# Aux_Board_V2.net
KiCad netlist of a schematic drawn in EAGLE
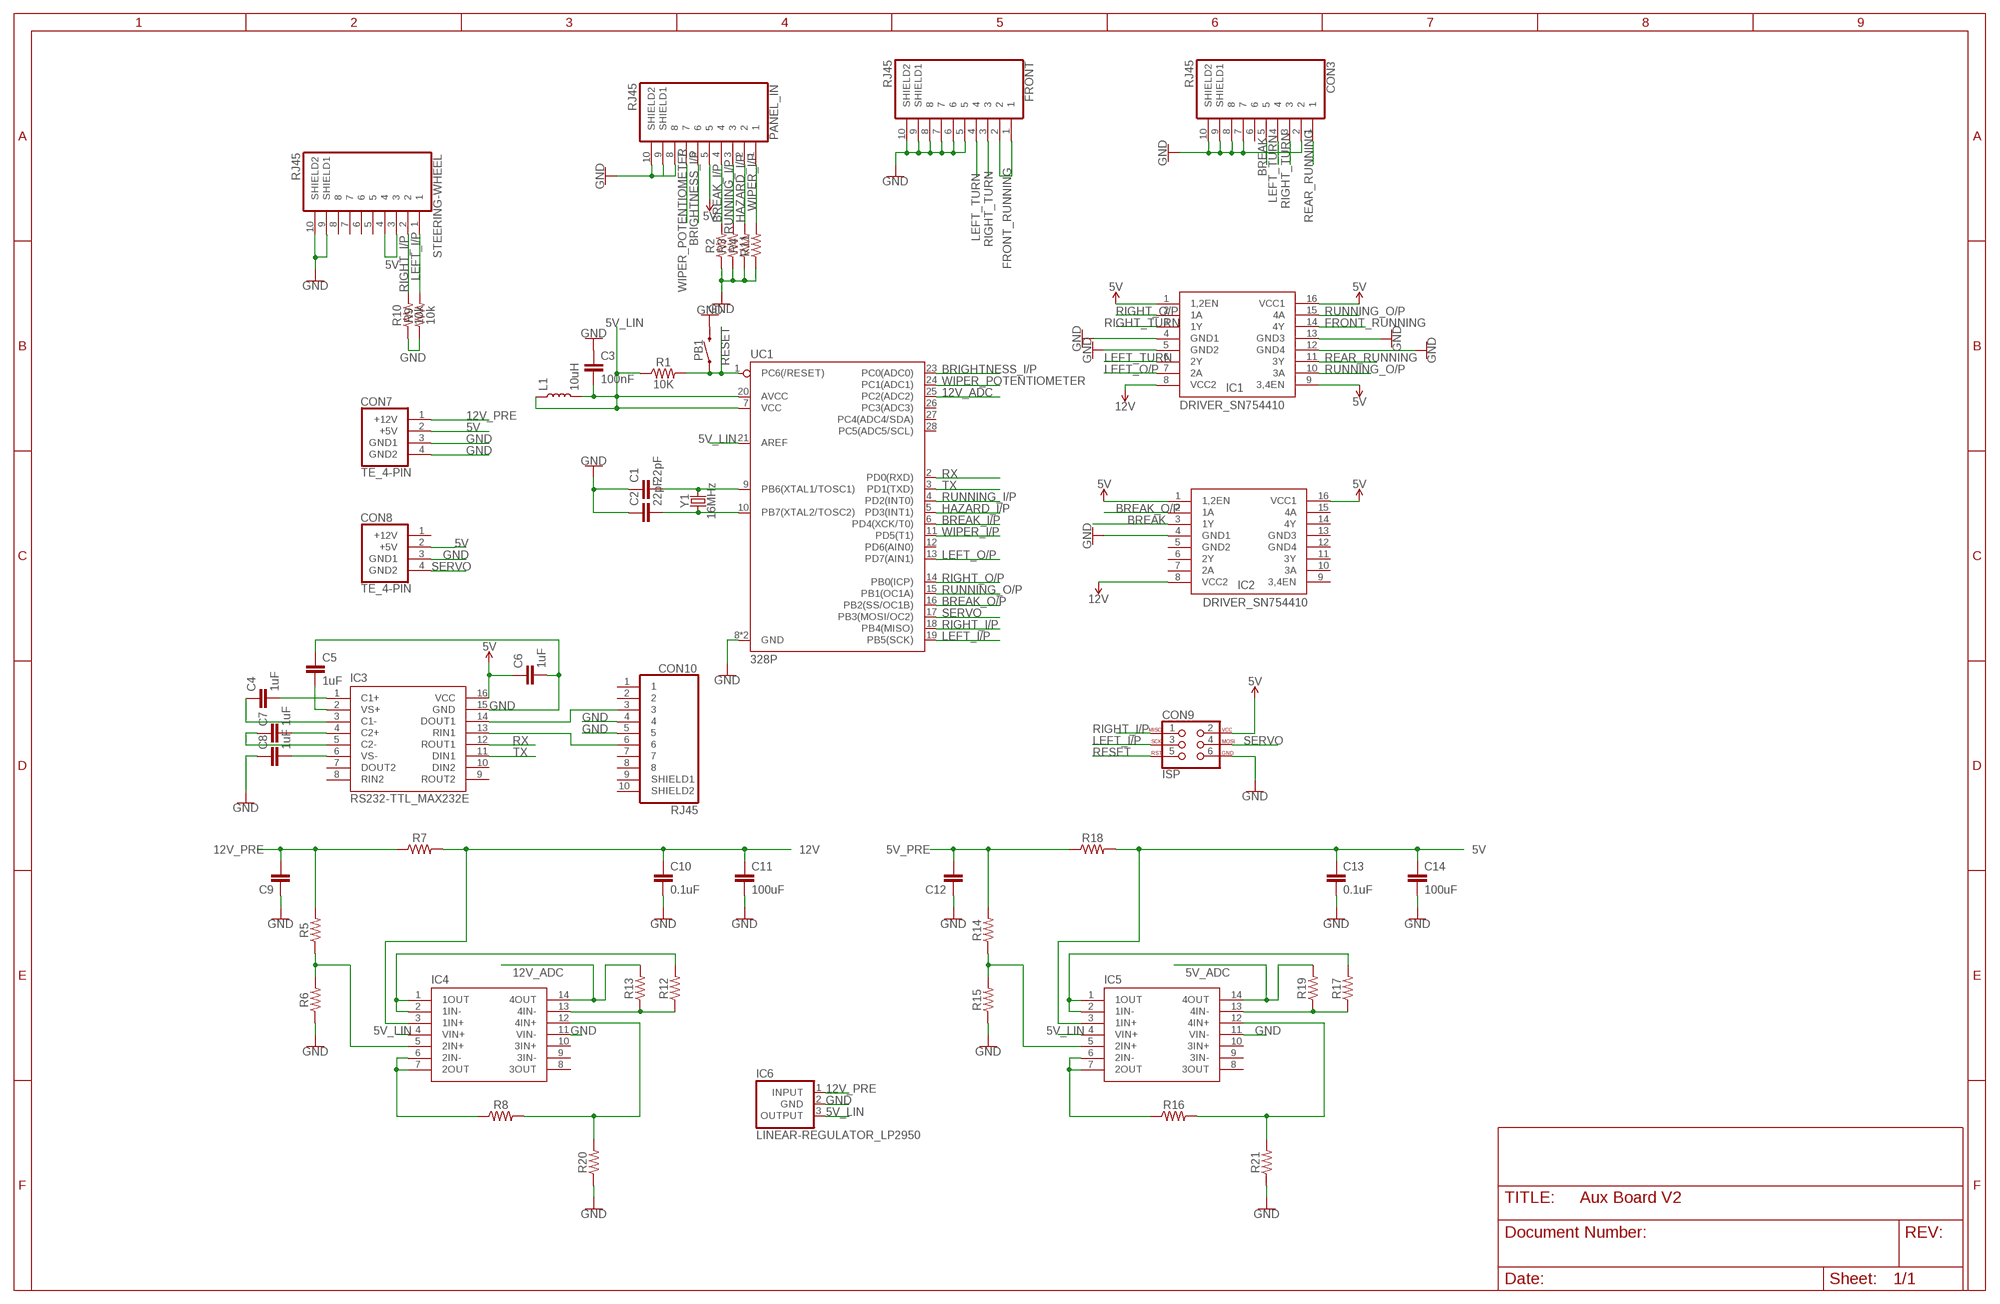
[diagram p0: schematic, sheet 1]

(export (version "E")
  (design (tool "Eeschema 10.0.6"))
  (components
    (comp (ref "C1")
      (value "22pF")
      (footprint "eagle-import:0805")
      (libsource (lib "eagle-import") (part "CAPACITOR_0805"))
    )
    (comp (ref "C2")
      (value "22pF")
      (footprint "eagle-import:0805")
      (libsource (lib "eagle-import") (part "CAPACITOR_0805"))
    )
    (comp (ref "C3")
      (value "100nF")
      (footprint "eagle-import:0805")
      (libsource (lib "eagle-import") (part "CAPACITOR_0805"))
    )
    (comp (ref "C4")
      (value "1uF")
      (footprint "eagle-import:0805")
      (libsource (lib "eagle-import") (part "CAPACITOR_0805"))
    )
    (comp (ref "C5")
      (value "1uF")
      (footprint "eagle-import:0805")
      (libsource (lib "eagle-import") (part "CAPACITOR_0805"))
    )
    (comp (ref "C6")
      (value "1uF")
      (footprint "eagle-import:0805")
      (libsource (lib "eagle-import") (part "CAPACITOR_0805"))
    )
    (comp (ref "C7")
      (value "1uF")
      (footprint "eagle-import:0805")
      (libsource (lib "eagle-import") (part "CAPACITOR_0805"))
    )
    (comp (ref "C8")
      (value "1uF")
      (footprint "eagle-import:0805")
      (libsource (lib "eagle-import") (part "CAPACITOR_0805"))
    )
    (comp (ref "C9")
      (value "CAPACITOR_0805")
      (footprint "eagle-import:0805")
      (libsource (lib "eagle-import") (part "CAPACITOR_0805"))
    )
    (comp (ref "C10")
      (value "0.1uF")
      (footprint "eagle-import:0805")
      (libsource (lib "eagle-import") (part "CAPACITOR_0805"))
    )
    (comp (ref "C11")
      (value "100uF")
      (footprint "eagle-import:0805")
      (libsource (lib "eagle-import") (part "CAPACITOR_0805"))
    )
    (comp (ref "C12")
      (value "CAPACITOR_0805")
      (footprint "eagle-import:0805")
      (libsource (lib "eagle-import") (part "CAPACITOR_0805"))
    )
    (comp (ref "C13")
      (value "0.1uF")
      (footprint "eagle-import:0805")
      (libsource (lib "eagle-import") (part "CAPACITOR_0805"))
    )
    (comp (ref "C14")
      (value "100uF")
      (footprint "eagle-import:0805")
      (libsource (lib "eagle-import") (part "CAPACITOR_0805"))
    )
    (comp (ref "CON3")
      (value "RJ45")
      (footprint "eagle-import:RJ45")
      (libsource (lib "eagle-import") (part "RJ45"))
    )
    (comp (ref "CON7")
      (value "TE_4-PIN")
      (footprint "eagle-import:TE_4-PIN")
      (libsource (lib "eagle-import") (part "TE_4-PIN"))
    )
    (comp (ref "CON8")
      (value "TE_4-PIN")
      (footprint "eagle-import:TE_4-PIN")
      (libsource (lib "eagle-import") (part "TE_4-PIN"))
    )
    (comp (ref "CON9")
      (value "ISP")
      (footprint "eagle-import:ISP_CONNECTOR")
      (libsource (lib "eagle-import") (part "ISP"))
    )
    (comp (ref "CON10")
      (value "RJ45")
      (footprint "eagle-import:RJ45")
      (libsource (lib "eagle-import") (part "RJ45"))
    )
    (comp (ref "FRONT")
      (value "RJ45")
      (footprint "eagle-import:RJ45")
      (libsource (lib "eagle-import") (part "RJ45"))
    )
    (comp (ref "IC1")
      (value "DRIVER_SN754410")
      (footprint "eagle-import:DIP16")
      (libsource (lib "eagle-import") (part "DRIVER_SN754410"))
    )
    (comp (ref "IC2")
      (value "DRIVER_SN754410")
      (footprint "eagle-import:DIP16")
      (libsource (lib "eagle-import") (part "DRIVER_SN754410"))
    )
    (comp (ref "IC3")
      (value "RS232-TTL_MAX232E")
      (footprint "eagle-import:DIP16")
      (libsource (lib "eagle-import") (part "RS232-TTL_MAX232E"))
    )
    (comp (ref "IC4")
      (value "OP-AMP_QUAD")
      (footprint "eagle-import:DIP14")
      (libsource (lib "eagle-import") (part "OP-AMP_QUAD"))
    )
    (comp (ref "IC5")
      (value "OP-AMP_QUAD")
      (footprint "eagle-import:DIP14")
      (libsource (lib "eagle-import") (part "OP-AMP_QUAD"))
    )
    (comp (ref "IC6")
      (value "LINEAR-REGULATOR_LP2950")
      (footprint "eagle-import:TO92")
      (libsource (lib "eagle-import") (part "LINEAR-REGULATOR_LP2950"))
    )
    (comp (ref "L1")
      (value "10uH")
      (footprint "eagle-import:0805")
      (libsource (lib "eagle-import") (part "INDUCTOR_0805"))
    )
    (comp (ref "PANEL_IN")
      (value "RJ45")
      (footprint "eagle-import:RJ45")
      (libsource (lib "eagle-import") (part "RJ45"))
    )
    (comp (ref "PB1")
      (value "PUSHBUTTON")
      (footprint "eagle-import:PUSHBUTTON")
      (libsource (lib "eagle-import") (part "PUSHBUTTON"))
    )
    (comp (ref "R1")
      (value "10K")
      (footprint "eagle-import:0805")
      (libsource (lib "eagle-import") (part "RESISTOR_0805"))
    )
    (comp (ref "R2")
      (value "RESISTOR_0805")
      (footprint "eagle-import:0805")
      (libsource (lib "eagle-import") (part "RESISTOR_0805"))
    )
    (comp (ref "R3")
      (value "RESISTOR_0805")
      (footprint "eagle-import:0805")
      (libsource (lib "eagle-import") (part "RESISTOR_0805"))
    )
    (comp (ref "R4")
      (value "RESISTOR_0805")
      (footprint "eagle-import:0805")
      (libsource (lib "eagle-import") (part "RESISTOR_0805"))
    )
    (comp (ref "R5")
      (value "RESISTOR_0805")
      (footprint "eagle-import:0805")
      (libsource (lib "eagle-import") (part "RESISTOR_0805"))
    )
    (comp (ref "R6")
      (value "RESISTOR_0805")
      (footprint "eagle-import:0805")
      (libsource (lib "eagle-import") (part "RESISTOR_0805"))
    )
    (comp (ref "R7")
      (value "RESISTOR_1210")
      (footprint "eagle-import:1210")
      (libsource (lib "eagle-import") (part "RESISTOR_1210"))
    )
    (comp (ref "R8")
      (value "RESISTOR_0805")
      (footprint "eagle-import:0805")
      (libsource (lib "eagle-import") (part "RESISTOR_0805"))
    )
    (comp (ref "R9")
      (value "10k")
      (footprint "eagle-import:0805")
      (libsource (lib "eagle-import") (part "RESISTOR_0805"))
    )
    (comp (ref "R10")
      (value "10k")
      (footprint "eagle-import:0805")
      (libsource (lib "eagle-import") (part "RESISTOR_0805"))
    )
    (comp (ref "R11")
      (value "RESISTOR_0805")
      (footprint "eagle-import:0805")
      (libsource (lib "eagle-import") (part "RESISTOR_0805"))
    )
    (comp (ref "R12")
      (value "RESISTOR_0805")
      (footprint "eagle-import:0805")
      (libsource (lib "eagle-import") (part "RESISTOR_0805"))
    )
    (comp (ref "R13")
      (value "RESISTOR_0805")
      (footprint "eagle-import:0805")
      (libsource (lib "eagle-import") (part "RESISTOR_0805"))
    )
    (comp (ref "R14")
      (value "RESISTOR_0805")
      (footprint "eagle-import:0805")
      (libsource (lib "eagle-import") (part "RESISTOR_0805"))
    )
    (comp (ref "R15")
      (value "RESISTOR_0805")
      (footprint "eagle-import:0805")
      (libsource (lib "eagle-import") (part "RESISTOR_0805"))
    )
    (comp (ref "R16")
      (value "RESISTOR_0805")
      (footprint "eagle-import:0805")
      (libsource (lib "eagle-import") (part "RESISTOR_0805"))
    )
    (comp (ref "R17")
      (value "RESISTOR_0805")
      (footprint "eagle-import:0805")
      (libsource (lib "eagle-import") (part "RESISTOR_0805"))
    )
    (comp (ref "R18")
      (value "RESISTOR_1210")
      (footprint "eagle-import:1210")
      (libsource (lib "eagle-import") (part "RESISTOR_1210"))
    )
    (comp (ref "R19")
      (value "RESISTOR_0805")
      (footprint "eagle-import:0805")
      (libsource (lib "eagle-import") (part "RESISTOR_0805"))
    )
    (comp (ref "R20")
      (value "RESISTOR_0805")
      (footprint "eagle-import:0805")
      (libsource (lib "eagle-import") (part "RESISTOR_0805"))
    )
    (comp (ref "R21")
      (value "RESISTOR_0805")
      (footprint "eagle-import:0805")
      (libsource (lib "eagle-import") (part "RESISTOR_0805"))
    )
    (comp (ref "STEERING-WHEEL")
      (value "RJ45")
      (footprint "eagle-import:RJ45")
      (libsource (lib "eagle-import") (part "RJ45"))
    )
    (comp (ref "UC1")
      (value "328P")
      (footprint "eagle-import:DIP28")
      (libsource (lib "eagle-import") (part "ATMEGA328P_DIP28"))
    )
    (comp (ref "Y1")
      (value "16MHz")
      (footprint "eagle-import:HC49US")
      (libsource (lib "eagle-import") (part "CRYSTAL-16MHZPTH-HC49US"))
    )
  )
  (nets
    (net (code "1") (name "/5V_ADC") (class "Default")
      (node (ref "IC5") (pin "14") (pinfunction "4OUT_14") (pintype "bidirectional"))
      (node (ref "R19") (pin "2") (pinfunction "2_2") (pintype "passive"))
    )
    (net (code "2") (name "/5V_LIN") (class "Default")
      (node (ref "C3") (pin "2") (pinfunction "2_2") (pintype "passive"))
      (node (ref "IC4") (pin "4") (pinfunction "VIN+_4") (pintype "bidirectional"))
      (node (ref "IC5") (pin "4") (pinfunction "VIN+_4") (pintype "bidirectional"))
      (node (ref "IC6") (pin "3") (pinfunction "OUTPUT_3") (pintype "bidirectional"))
      (node (ref "L1") (pin "1") (pinfunction "1_1") (pintype "passive"))
      (node (ref "L1") (pin "2") (pinfunction "2_2") (pintype "passive"))
      (node (ref "R1") (pin "1") (pinfunction "1_1") (pintype "passive"))
      (node (ref "UC1") (pin "20") (pinfunction "AVCC_20") (pintype "bidirectional"))
      (node (ref "UC1") (pin "21") (pinfunction "AREF_21") (pintype "bidirectional"))
      (node (ref "UC1") (pin "7") (pinfunction "VCC_7") (pintype "bidirectional"))
    )
    (net (code "3") (name "/5V_PRE") (class "Default")
      (node (ref "C12") (pin "2") (pinfunction "2_2") (pintype "passive"))
      (node (ref "R14") (pin "2") (pinfunction "2_2") (pintype "passive"))
      (node (ref "R18") (pin "1") (pinfunction "1_1") (pintype "passive"))
    )
    (net (code "4") (name "/12V_ADC") (class "Default")
      (node (ref "IC4") (pin "14") (pinfunction "4OUT_14") (pintype "bidirectional"))
      (node (ref "R13") (pin "2") (pinfunction "2_2") (pintype "passive"))
      (node (ref "UC1") (pin "25") (pinfunction "PC2(ADC2)_25") (pintype "bidirectional"))
    )
    (net (code "5") (name "/12V_PRE") (class "Default")
      (node (ref "C9") (pin "2") (pinfunction "2_2") (pintype "passive"))
      (node (ref "CON7") (pin "1") (pinfunction "+12V_1") (pintype "passive"))
      (node (ref "IC6") (pin "1") (pinfunction "INPUT_1") (pintype "bidirectional"))
      (node (ref "R5") (pin "2") (pinfunction "2_2") (pintype "passive"))
      (node (ref "R7") (pin "1") (pinfunction "1_1") (pintype "passive"))
    )
    (net (code "6") (name "/BREAK") (class "Default")
      (node (ref "CON3") (pin "5") (pinfunction "5_5") (pintype "passive"))
      (node (ref "IC2") (pin "3") (pinfunction "1Y_3") (pintype "bidirectional"))
    )
    (net (code "7") (name "/BREAK_I{slash}P") (class "Default")
      (node (ref "PANEL_IN") (pin "4") (pinfunction "4_4") (pintype "passive"))
      (node (ref "R2") (pin "2") (pinfunction "2_2") (pintype "passive"))
      (node (ref "UC1") (pin "6") (pinfunction "PD4(XCK/T0)_6") (pintype "bidirectional"))
    )
    (net (code "8") (name "/BREAK_O{slash}P") (class "Default")
      (node (ref "IC2") (pin "2") (pinfunction "1A_2") (pintype "bidirectional"))
      (node (ref "UC1") (pin "16") (pinfunction "PB2(SS/OC1B)_16") (pintype "bidirectional"))
    )
    (net (code "9") (name "/BRIGHTNESS_I{slash}P") (class "Default")
      (node (ref "PANEL_IN") (pin "6") (pinfunction "6_6") (pintype "passive"))
      (node (ref "UC1") (pin "23") (pinfunction "PC0(ADC0)_23") (pintype "bidirectional"))
    )
    (net (code "10") (name "/FRONT_RUNNING") (class "Default")
      (node (ref "FRONT") (pin "1") (pinfunction "1_1") (pintype "passive"))
      (node (ref "FRONT") (pin "2") (pinfunction "2_2") (pintype "passive"))
      (node (ref "IC1") (pin "14") (pinfunction "4Y_14") (pintype "bidirectional"))
    )
    (net (code "11") (name "/HAZARD_I{slash}P") (class "Default")
      (node (ref "PANEL_IN") (pin "2") (pinfunction "2_2") (pintype "passive"))
      (node (ref "R4") (pin "2") (pinfunction "2_2") (pintype "passive"))
      (node (ref "UC1") (pin "5") (pinfunction "PD3(INT1)_5") (pintype "bidirectional"))
    )
    (net (code "12") (name "/LEFT_I{slash}P") (class "Default")
      (node (ref "CON9") (pin "3") (pinfunction "3_3") (pintype "passive"))
      (node (ref "R9") (pin "2") (pinfunction "2_2") (pintype "passive"))
      (node (ref "STEERING-WHEEL") (pin "1") (pinfunction "1_1") (pintype "passive"))
      (node (ref "UC1") (pin "19") (pinfunction "PB5(SCK)_19") (pintype "bidirectional"))
    )
    (net (code "13") (name "/LEFT_O{slash}P") (class "Default")
      (node (ref "IC1") (pin "7") (pinfunction "2A_7") (pintype "bidirectional"))
      (node (ref "UC1") (pin "13") (pinfunction "PD7(AIN1)_13") (pintype "bidirectional"))
    )
    (net (code "14") (name "/LEFT_TURN") (class "Default")
      (node (ref "CON3") (pin "4") (pinfunction "4_4") (pintype "passive"))
      (node (ref "FRONT") (pin "4") (pinfunction "4_4") (pintype "passive"))
      (node (ref "IC1") (pin "6") (pinfunction "2Y_6") (pintype "bidirectional"))
    )
    (net (code "15") (name "/REAR_RUNNING") (class "Default")
      (node (ref "CON3") (pin "1") (pinfunction "1_1") (pintype "passive"))
      (node (ref "IC1") (pin "11") (pinfunction "3Y_11") (pintype "bidirectional"))
    )
    (net (code "16") (name "/RESET") (class "Default")
      (node (ref "CON9") (pin "5") (pinfunction "5_5") (pintype "passive"))
      (node (ref "PB1") (pin "1") (pinfunction "1_1") (pintype "passive"))
      (node (ref "PB1") (pin "2") (pinfunction "1_2") (pintype "passive"))
      (node (ref "R1") (pin "2") (pinfunction "2_2") (pintype "passive"))
      (node (ref "UC1") (pin "1") (pinfunction "PC6(/RESET)_1") (pintype "bidirectional"))
    )
    (net (code "17") (name "/RIGHT_I{slash}P") (class "Default")
      (node (ref "CON9") (pin "1") (pinfunction "1_1") (pintype "passive"))
      (node (ref "R10") (pin "2") (pinfunction "2_2") (pintype "passive"))
      (node (ref "STEERING-WHEEL") (pin "2") (pinfunction "2_2") (pintype "passive"))
      (node (ref "UC1") (pin "18") (pinfunction "PB4(MISO)_18") (pintype "bidirectional"))
    )
    (net (code "18") (name "/RIGHT_O{slash}P") (class "Default")
      (node (ref "IC1") (pin "2") (pinfunction "1A_2") (pintype "bidirectional"))
      (node (ref "UC1") (pin "14") (pinfunction "PB0(ICP)_14") (pintype "bidirectional"))
    )
    (net (code "19") (name "/RIGHT_TURN") (class "Default")
      (node (ref "CON3") (pin "3") (pinfunction "3_3") (pintype "passive"))
      (node (ref "FRONT") (pin "3") (pinfunction "3_3") (pintype "passive"))
      (node (ref "IC1") (pin "3") (pinfunction "1Y_3") (pintype "bidirectional"))
    )
    (net (code "20") (name "/RUNNING_I{slash}P") (class "Default")
      (node (ref "PANEL_IN") (pin "3") (pinfunction "3_3") (pintype "passive"))
      (node (ref "R3") (pin "2") (pinfunction "2_2") (pintype "passive"))
      (node (ref "UC1") (pin "4") (pinfunction "PD2(INT0)_4") (pintype "bidirectional"))
    )
    (net (code "21") (name "/RUNNING_O{slash}P") (class "Default")
      (node (ref "IC1") (pin "10") (pinfunction "3A_10") (pintype "bidirectional"))
      (node (ref "IC1") (pin "15") (pinfunction "4A_15") (pintype "bidirectional"))
      (node (ref "UC1") (pin "15") (pinfunction "PB1(OC1A)_15") (pintype "bidirectional"))
    )
    (net (code "22") (name "/RX") (class "Default")
      (node (ref "IC3") (pin "12") (pinfunction "ROUT1_12") (pintype "bidirectional"))
      (node (ref "UC1") (pin "2") (pinfunction "PD0(RXD)_2") (pintype "bidirectional"))
    )
    (net (code "23") (name "/SERVO") (class "Default")
      (node (ref "CON8") (pin "4") (pinfunction "GND2_4") (pintype "passive"))
      (node (ref "CON9") (pin "4") (pinfunction "4_4") (pintype "passive"))
      (node (ref "UC1") (pin "17") (pinfunction "PB3(MOSI/OC2)_17") (pintype "bidirectional"))
    )
    (net (code "24") (name "/TX") (class "Default")
      (node (ref "IC3") (pin "11") (pinfunction "DIN1_11") (pintype "bidirectional"))
      (node (ref "UC1") (pin "3") (pinfunction "PD1(TXD)_3") (pintype "bidirectional"))
    )
    (net (code "25") (name "/WIPER_I{slash}P") (class "Default")
      (node (ref "PANEL_IN") (pin "1") (pinfunction "1_1") (pintype "passive"))
      (node (ref "R11") (pin "2") (pinfunction "2_2") (pintype "passive"))
      (node (ref "UC1") (pin "11") (pinfunction "PD5(T1)_11") (pintype "bidirectional"))
    )
    (net (code "26") (name "/WIPER_POTENTIOMETER") (class "Default")
      (node (ref "PANEL_IN") (pin "7") (pinfunction "7_7") (pintype "passive"))
      (node (ref "UC1") (pin "24") (pinfunction "PC1(ADC1)_24") (pintype "bidirectional"))
    )
    (net (code "27") (name "5V") (class "Default")
      (node (ref "C13") (pin "1") (pinfunction "1_1") (pintype "passive"))
      (node (ref "C14") (pin "1") (pinfunction "1_1") (pintype "passive"))
      (node (ref "C6") (pin "1") (pinfunction "1_1") (pintype "passive"))
      (node (ref "CON7") (pin "2") (pinfunction "+5V_2") (pintype "passive"))
      (node (ref "CON8") (pin "2") (pinfunction "+5V_2") (pintype "passive"))
      (node (ref "CON9") (pin "2") (pinfunction "2_2") (pintype "passive"))
      (node (ref "IC1") (pin "1") (pinfunction "1,2EN_1") (pintype "bidirectional"))
      (node (ref "IC1") (pin "16") (pinfunction "VCC1_16") (pintype "bidirectional"))
      (node (ref "IC1") (pin "9") (pinfunction "3,4EN_9") (pintype "bidirectional"))
      (node (ref "IC2") (pin "1") (pinfunction "1,2EN_1") (pintype "bidirectional"))
      (node (ref "IC2") (pin "16") (pinfunction "VCC1_16") (pintype "bidirectional"))
      (node (ref "IC3") (pin "16") (pinfunction "VCC_16") (pintype "bidirectional"))
      (node (ref "IC5") (pin "3") (pinfunction "1IN+_3") (pintype "bidirectional"))
      (node (ref "PANEL_IN") (pin "5") (pinfunction "5_5") (pintype "passive"))
      (node (ref "R18") (pin "2") (pinfunction "2_2") (pintype "passive"))
      (node (ref "STEERING-WHEEL") (pin "3") (pinfunction "3_3") (pintype "passive"))
      (node (ref "STEERING-WHEEL") (pin "4") (pinfunction "4_4") (pintype "passive"))
    )
    (net (code "28") (name "12V") (class "Default")
      (node (ref "C10") (pin "1") (pinfunction "1_1") (pintype "passive"))
      (node (ref "C11") (pin "1") (pinfunction "1_1") (pintype "passive"))
      (node (ref "IC1") (pin "8") (pinfunction "VCC2_8") (pintype "bidirectional"))
      (node (ref "IC2") (pin "8") (pinfunction "VCC2_8") (pintype "bidirectional"))
      (node (ref "IC4") (pin "3") (pinfunction "1IN+_3") (pintype "bidirectional"))
      (node (ref "R7") (pin "2") (pinfunction "2_2") (pintype "passive"))
    )
    (net (code "29") (name "GND") (class "Default")
      (node (ref "C1") (pin "1") (pinfunction "1_1") (pintype "passive"))
      (node (ref "C10") (pin "2") (pinfunction "2_2") (pintype "passive"))
      (node (ref "C11") (pin "2") (pinfunction "2_2") (pintype "passive"))
      (node (ref "C12") (pin "1") (pinfunction "1_1") (pintype "passive"))
      (node (ref "C13") (pin "2") (pinfunction "2_2") (pintype "passive"))
      (node (ref "C14") (pin "2") (pinfunction "2_2") (pintype "passive"))
      (node (ref "C2") (pin "1") (pinfunction "1_1") (pintype "passive"))
      (node (ref "C3") (pin "1") (pinfunction "1_1") (pintype "passive"))
      (node (ref "C5") (pin "1") (pinfunction "1_1") (pintype "passive"))
      (node (ref "C6") (pin "2") (pinfunction "2_2") (pintype "passive"))
      (node (ref "C8") (pin "1") (pinfunction "1_1") (pintype "passive"))
      (node (ref "C9") (pin "1") (pinfunction "1_1") (pintype "passive"))
      (node (ref "CON10") (pin "4") (pinfunction "4_4") (pintype "passive"))
      (node (ref "CON10") (pin "5") (pinfunction "5_5") (pintype "passive"))
      (node (ref "CON3") (pin "10") (pinfunction "SHIELD2_10") (pintype "passive"))
      (node (ref "CON3") (pin "2") (pinfunction "2_2") (pintype "passive"))
      (node (ref "CON3") (pin "7") (pinfunction "7_7") (pintype "passive"))
      (node (ref "CON3") (pin "8") (pinfunction "8_8") (pintype "passive"))
      (node (ref "CON3") (pin "9") (pinfunction "SHIELD1_9") (pintype "passive"))
      (node (ref "CON7") (pin "3") (pinfunction "GND1_3") (pintype "passive"))
      (node (ref "CON7") (pin "4") (pinfunction "GND2_4") (pintype "passive"))
      (node (ref "CON8") (pin "3") (pinfunction "GND1_3") (pintype "passive"))
      (node (ref "CON9") (pin "6") (pinfunction "6_6") (pintype "passive"))
      (node (ref "FRONT") (pin "10") (pinfunction "SHIELD2_10") (pintype "passive"))
      (node (ref "FRONT") (pin "5") (pinfunction "5_5") (pintype "passive"))
      (node (ref "FRONT") (pin "6") (pinfunction "6_6") (pintype "passive"))
      (node (ref "FRONT") (pin "7") (pinfunction "7_7") (pintype "passive"))
      (node (ref "FRONT") (pin "8") (pinfunction "8_8") (pintype "passive"))
      (node (ref "FRONT") (pin "9") (pinfunction "SHIELD1_9") (pintype "passive"))
      (node (ref "IC1") (pin "12") (pinfunction "GND4_12") (pintype "bidirectional"))
      (node (ref "IC1") (pin "13") (pinfunction "GND3_13") (pintype "bidirectional"))
      (node (ref "IC1") (pin "4") (pinfunction "GND1_4") (pintype "bidirectional"))
      (node (ref "IC1") (pin "5") (pinfunction "GND2_5") (pintype "bidirectional"))
      (node (ref "IC2") (pin "4") (pinfunction "GND1_4") (pintype "bidirectional"))
      (node (ref "IC3") (pin "15") (pinfunction "GND_15") (pintype "bidirectional"))
      (node (ref "IC4") (pin "11") (pinfunction "VIN-_11") (pintype "bidirectional"))
      (node (ref "IC5") (pin "11") (pinfunction "VIN-_11") (pintype "bidirectional"))
      (node (ref "IC6") (pin "2") (pinfunction "GND_2") (pintype "bidirectional"))
      (node (ref "PANEL_IN") (pin "10") (pinfunction "SHIELD2_10") (pintype "passive"))
      (node (ref "PANEL_IN") (pin "8") (pinfunction "8_8") (pintype "passive"))
      (node (ref "PANEL_IN") (pin "9") (pinfunction "SHIELD1_9") (pintype "passive"))
      (node (ref "PB1") (pin "3") (pinfunction "2_3") (pintype "passive"))
      (node (ref "PB1") (pin "4") (pinfunction "2_4") (pintype "passive"))
      (node (ref "R10") (pin "1") (pinfunction "1_1") (pintype "passive"))
      (node (ref "R11") (pin "1") (pinfunction "1_1") (pintype "passive"))
      (node (ref "R15") (pin "1") (pinfunction "1_1") (pintype "passive"))
      (node (ref "R2") (pin "1") (pinfunction "1_1") (pintype "passive"))
      (node (ref "R20") (pin "1") (pinfunction "1_1") (pintype "passive"))
      (node (ref "R21") (pin "1") (pinfunction "1_1") (pintype "passive"))
      (node (ref "R3") (pin "1") (pinfunction "1_1") (pintype "passive"))
      (node (ref "R4") (pin "1") (pinfunction "1_1") (pintype "passive"))
      (node (ref "R6") (pin "1") (pinfunction "1_1") (pintype "passive"))
      (node (ref "R9") (pin "1") (pinfunction "1_1") (pintype "passive"))
      (node (ref "STEERING-WHEEL") (pin "10") (pinfunction "SHIELD2_10") (pintype "passive"))
      (node (ref "STEERING-WHEEL") (pin "9") (pinfunction "SHIELD1_9") (pintype "passive"))
      (node (ref "UC1") (pin "22") (pinfunction "GND_22") (pintype "bidirectional"))
      (node (ref "UC1") (pin "8") (pinfunction "GND_8") (pintype "bidirectional"))
    )
    (net (code "30") (name "Net-(IC3-C1+)") (class "Default")
      (node (ref "C4") (pin "2") (pinfunction "2_2") (pintype "passive"))
      (node (ref "IC3") (pin "1") (pinfunction "C1+_1") (pintype "bidirectional"))
    )
    (net (code "31") (name "Net-(IC3-C1-)") (class "Default")
      (node (ref "C4") (pin "1") (pinfunction "1_1") (pintype "passive"))
      (node (ref "IC3") (pin "3") (pinfunction "C1-_3") (pintype "bidirectional"))
    )
    (net (code "32") (name "Net-(IC3-C2+)") (class "Default")
      (node (ref "C7") (pin "2") (pinfunction "2_2") (pintype "passive"))
      (node (ref "IC3") (pin "4") (pinfunction "C2+_4") (pintype "bidirectional"))
    )
    (net (code "33") (name "Net-(IC3-C2-)") (class "Default")
      (node (ref "C7") (pin "1") (pinfunction "1_1") (pintype "passive"))
      (node (ref "IC3") (pin "5") (pinfunction "C2-_5") (pintype "bidirectional"))
    )
    (net (code "34") (name "Net-(IC3-DOUT1)") (class "Default")
      (node (ref "CON10") (pin "3") (pinfunction "3_3") (pintype "passive"))
      (node (ref "IC3") (pin "14") (pinfunction "DOUT1_14") (pintype "bidirectional"))
    )
    (net (code "35") (name "Net-(IC3-RIN1)") (class "Default")
      (node (ref "CON10") (pin "6") (pinfunction "6_6") (pintype "passive"))
      (node (ref "IC3") (pin "13") (pinfunction "RIN1_13") (pintype "bidirectional"))
    )
    (net (code "36") (name "Net-(IC3-VS+)") (class "Default")
      (node (ref "C5") (pin "2") (pinfunction "2_2") (pintype "passive"))
      (node (ref "IC3") (pin "2") (pinfunction "VS+_2") (pintype "bidirectional"))
    )
    (net (code "37") (name "Net-(IC3-VS-)") (class "Default")
      (node (ref "C8") (pin "2") (pinfunction "2_2") (pintype "passive"))
      (node (ref "IC3") (pin "6") (pinfunction "VS-_6") (pintype "bidirectional"))
    )
    (net (code "38") (name "Net-(IC4-1IN-)") (class "Default")
      (node (ref "IC4") (pin "1") (pinfunction "1OUT_1") (pintype "bidirectional"))
      (node (ref "IC4") (pin "2") (pinfunction "1IN-_2") (pintype "bidirectional"))
      (node (ref "R12") (pin "2") (pinfunction "2_2") (pintype "passive"))
    )
    (net (code "39") (name "Net-(IC4-2IN+)") (class "Default")
      (node (ref "IC4") (pin "5") (pinfunction "2IN+_5") (pintype "bidirectional"))
      (node (ref "R5") (pin "1") (pinfunction "1_1") (pintype "passive"))
      (node (ref "R6") (pin "2") (pinfunction "2_2") (pintype "passive"))
    )
    (net (code "40") (name "Net-(IC4-2IN-)") (class "Default")
      (node (ref "IC4") (pin "6") (pinfunction "2IN-_6") (pintype "bidirectional"))
      (node (ref "IC4") (pin "7") (pinfunction "2OUT_7") (pintype "bidirectional"))
      (node (ref "R8") (pin "1") (pinfunction "1_1") (pintype "passive"))
    )
    (net (code "41") (name "Net-(IC4-4IN+)") (class "Default")
      (node (ref "IC4") (pin "12") (pinfunction "4IN+_12") (pintype "bidirectional"))
      (node (ref "R20") (pin "2") (pinfunction "2_2") (pintype "passive"))
      (node (ref "R8") (pin "2") (pinfunction "2_2") (pintype "passive"))
    )
    (net (code "42") (name "Net-(IC4-4IN-)") (class "Default")
      (node (ref "IC4") (pin "13") (pinfunction "4IN-_13") (pintype "bidirectional"))
      (node (ref "R12") (pin "1") (pinfunction "1_1") (pintype "passive"))
      (node (ref "R13") (pin "1") (pinfunction "1_1") (pintype "passive"))
    )
    (net (code "43") (name "Net-(IC5-1IN-)") (class "Default")
      (node (ref "IC5") (pin "1") (pinfunction "1OUT_1") (pintype "bidirectional"))
      (node (ref "IC5") (pin "2") (pinfunction "1IN-_2") (pintype "bidirectional"))
      (node (ref "R17") (pin "2") (pinfunction "2_2") (pintype "passive"))
    )
    (net (code "44") (name "Net-(IC5-2IN+)") (class "Default")
      (node (ref "IC5") (pin "5") (pinfunction "2IN+_5") (pintype "bidirectional"))
      (node (ref "R14") (pin "1") (pinfunction "1_1") (pintype "passive"))
      (node (ref "R15") (pin "2") (pinfunction "2_2") (pintype "passive"))
    )
    (net (code "45") (name "Net-(IC5-2IN-)") (class "Default")
      (node (ref "IC5") (pin "6") (pinfunction "2IN-_6") (pintype "bidirectional"))
      (node (ref "IC5") (pin "7") (pinfunction "2OUT_7") (pintype "bidirectional"))
      (node (ref "R16") (pin "1") (pinfunction "1_1") (pintype "passive"))
    )
    (net (code "46") (name "Net-(IC5-4IN+)") (class "Default")
      (node (ref "IC5") (pin "12") (pinfunction "4IN+_12") (pintype "bidirectional"))
      (node (ref "R16") (pin "2") (pinfunction "2_2") (pintype "passive"))
      (node (ref "R21") (pin "2") (pinfunction "2_2") (pintype "passive"))
    )
    (net (code "47") (name "Net-(IC5-4IN-)") (class "Default")
      (node (ref "IC5") (pin "13") (pinfunction "4IN-_13") (pintype "bidirectional"))
      (node (ref "R17") (pin "1") (pinfunction "1_1") (pintype "passive"))
      (node (ref "R19") (pin "1") (pinfunction "1_1") (pintype "passive"))
    )
    (net (code "48") (name "Net-(UC1-PB6(XTAL1{slash}TOSC1))") (class "Default")
      (node (ref "C1") (pin "2") (pinfunction "2_2") (pintype "passive"))
      (node (ref "UC1") (pin "9") (pinfunction "PB6(XTAL1/TOSC1)_9") (pintype "bidirectional"))
      (node (ref "Y1") (pin "2") (pinfunction "2_2") (pintype "passive"))
    )
    (net (code "49") (name "Net-(UC1-PB7(XTAL2{slash}TOSC2))") (class "Default")
      (node (ref "C2") (pin "2") (pinfunction "2_2") (pintype "passive"))
      (node (ref "UC1") (pin "10") (pinfunction "PB7(XTAL2/TOSC2)_10") (pintype "bidirectional"))
      (node (ref "Y1") (pin "1") (pinfunction "1_1") (pintype "passive"))
    )
    (net (code "50") (name "unconnected-(CON3-Pad6)") (class "Default")
      (node (ref "CON3") (pin "6") (pinfunction "6_6") (pintype "passive"))
    )
    (net (code "51") (name "unconnected-(CON8-+12V-Pad1)") (class "Default")
      (node (ref "CON8") (pin "1") (pinfunction "+12V_1") (pintype "passive"))
    )
    (net (code "52") (name "unconnected-(CON10-Pad1)") (class "Default")
      (node (ref "CON10") (pin "1") (pinfunction "1_1") (pintype "passive"))
    )
    (net (code "53") (name "unconnected-(CON10-Pad2)") (class "Default")
      (node (ref "CON10") (pin "2") (pinfunction "2_2") (pintype "passive"))
    )
    (net (code "54") (name "unconnected-(CON10-Pad7)") (class "Default")
      (node (ref "CON10") (pin "7") (pinfunction "7_7") (pintype "passive"))
    )
    (net (code "55") (name "unconnected-(CON10-Pad8)") (class "Default")
      (node (ref "CON10") (pin "8") (pinfunction "8_8") (pintype "passive"))
    )
    (net (code "56") (name "unconnected-(CON10-SHIELD1-Pad9)") (class "Default")
      (node (ref "CON10") (pin "9") (pinfunction "SHIELD1_9") (pintype "passive"))
    )
    (net (code "57") (name "unconnected-(CON10-SHIELD2-Pad10)") (class "Default")
      (node (ref "CON10") (pin "10") (pinfunction "SHIELD2_10") (pintype "passive"))
    )
    (net (code "58") (name "unconnected-(IC2-2A-Pad7)") (class "Default")
      (node (ref "IC2") (pin "7") (pinfunction "2A_7") (pintype "bidirectional"))
    )
    (net (code "59") (name "unconnected-(IC2-2Y-Pad6)") (class "Default")
      (node (ref "IC2") (pin "6") (pinfunction "2Y_6") (pintype "bidirectional"))
    )
    (net (code "60") (name "unconnected-(IC2-3,4EN-Pad9)") (class "Default")
      (node (ref "IC2") (pin "9") (pinfunction "3,4EN_9") (pintype "bidirectional"))
    )
    (net (code "61") (name "unconnected-(IC2-3A-Pad10)") (class "Default")
      (node (ref "IC2") (pin "10") (pinfunction "3A_10") (pintype "bidirectional"))
    )
    (net (code "62") (name "unconnected-(IC2-3Y-Pad11)") (class "Default")
      (node (ref "IC2") (pin "11") (pinfunction "3Y_11") (pintype "bidirectional"))
    )
    (net (code "63") (name "unconnected-(IC2-4A-Pad15)") (class "Default")
      (node (ref "IC2") (pin "15") (pinfunction "4A_15") (pintype "bidirectional"))
    )
    (net (code "64") (name "unconnected-(IC2-4Y-Pad14)") (class "Default")
      (node (ref "IC2") (pin "14") (pinfunction "4Y_14") (pintype "bidirectional"))
    )
    (net (code "65") (name "unconnected-(IC2-GND2-Pad5)") (class "Default")
      (node (ref "IC2") (pin "5") (pinfunction "GND2_5") (pintype "bidirectional"))
    )
    (net (code "66") (name "unconnected-(IC2-GND3-Pad13)") (class "Default")
      (node (ref "IC2") (pin "13") (pinfunction "GND3_13") (pintype "bidirectional"))
    )
    (net (code "67") (name "unconnected-(IC2-GND4-Pad12)") (class "Default")
      (node (ref "IC2") (pin "12") (pinfunction "GND4_12") (pintype "bidirectional"))
    )
    (net (code "68") (name "unconnected-(IC3-DIN2-Pad10)") (class "Default")
      (node (ref "IC3") (pin "10") (pinfunction "DIN2_10") (pintype "bidirectional"))
    )
    (net (code "69") (name "unconnected-(IC3-DOUT2-Pad7)") (class "Default")
      (node (ref "IC3") (pin "7") (pinfunction "DOUT2_7") (pintype "bidirectional"))
    )
    (net (code "70") (name "unconnected-(IC3-RIN2-Pad8)") (class "Default")
      (node (ref "IC3") (pin "8") (pinfunction "RIN2_8") (pintype "bidirectional"))
    )
    (net (code "71") (name "unconnected-(IC3-ROUT2-Pad9)") (class "Default")
      (node (ref "IC3") (pin "9") (pinfunction "ROUT2_9") (pintype "bidirectional"))
    )
    (net (code "72") (name "unconnected-(IC4-3IN+-Pad10)") (class "Default")
      (node (ref "IC4") (pin "10") (pinfunction "3IN+_10") (pintype "bidirectional"))
    )
    (net (code "73") (name "unconnected-(IC4-3IN--Pad9)") (class "Default")
      (node (ref "IC4") (pin "9") (pinfunction "3IN-_9") (pintype "bidirectional"))
    )
    (net (code "74") (name "unconnected-(IC4-3OUT-Pad8)") (class "Default")
      (node (ref "IC4") (pin "8") (pinfunction "3OUT_8") (pintype "bidirectional"))
    )
    (net (code "75") (name "unconnected-(IC5-3IN+-Pad10)") (class "Default")
      (node (ref "IC5") (pin "10") (pinfunction "3IN+_10") (pintype "bidirectional"))
    )
    (net (code "76") (name "unconnected-(IC5-3IN--Pad9)") (class "Default")
      (node (ref "IC5") (pin "9") (pinfunction "3IN-_9") (pintype "bidirectional"))
    )
    (net (code "77") (name "unconnected-(IC5-3OUT-Pad8)") (class "Default")
      (node (ref "IC5") (pin "8") (pinfunction "3OUT_8") (pintype "bidirectional"))
    )
    (net (code "78") (name "unconnected-(STEERING-WHEEL-Pad5)") (class "Default")
      (node (ref "STEERING-WHEEL") (pin "5") (pinfunction "5_5") (pintype "passive"))
    )
    (net (code "79") (name "unconnected-(STEERING-WHEEL-Pad6)") (class "Default")
      (node (ref "STEERING-WHEEL") (pin "6") (pinfunction "6_6") (pintype "passive"))
    )
    (net (code "80") (name "unconnected-(STEERING-WHEEL-Pad7)") (class "Default")
      (node (ref "STEERING-WHEEL") (pin "7") (pinfunction "7_7") (pintype "passive"))
    )
    (net (code "81") (name "unconnected-(STEERING-WHEEL-Pad8)") (class "Default")
      (node (ref "STEERING-WHEEL") (pin "8") (pinfunction "8_8") (pintype "passive"))
    )
    (net (code "82") (name "unconnected-(UC1-PC3(ADC3)-Pad26)") (class "Default")
      (node (ref "UC1") (pin "26") (pinfunction "PC3(ADC3)_26") (pintype "bidirectional"))
    )
    (net (code "83") (name "unconnected-(UC1-PC4(ADC4{slash}SDA)-Pad27)") (class "Default")
      (node (ref "UC1") (pin "27") (pinfunction "PC4(ADC4/SDA)_27") (pintype "bidirectional"))
    )
    (net (code "84") (name "unconnected-(UC1-PC5(ADC5{slash}SCL)-Pad28)") (class "Default")
      (node (ref "UC1") (pin "28") (pinfunction "PC5(ADC5/SCL)_28") (pintype "bidirectional"))
    )
    (net (code "85") (name "unconnected-(UC1-PD6(AIN0)-Pad12)") (class "Default")
      (node (ref "UC1") (pin "12") (pinfunction "PD6(AIN0)_12") (pintype "bidirectional"))
    )
  )
)
